# smash.net
KiCad netlist of a schematic drawn in EAGLE
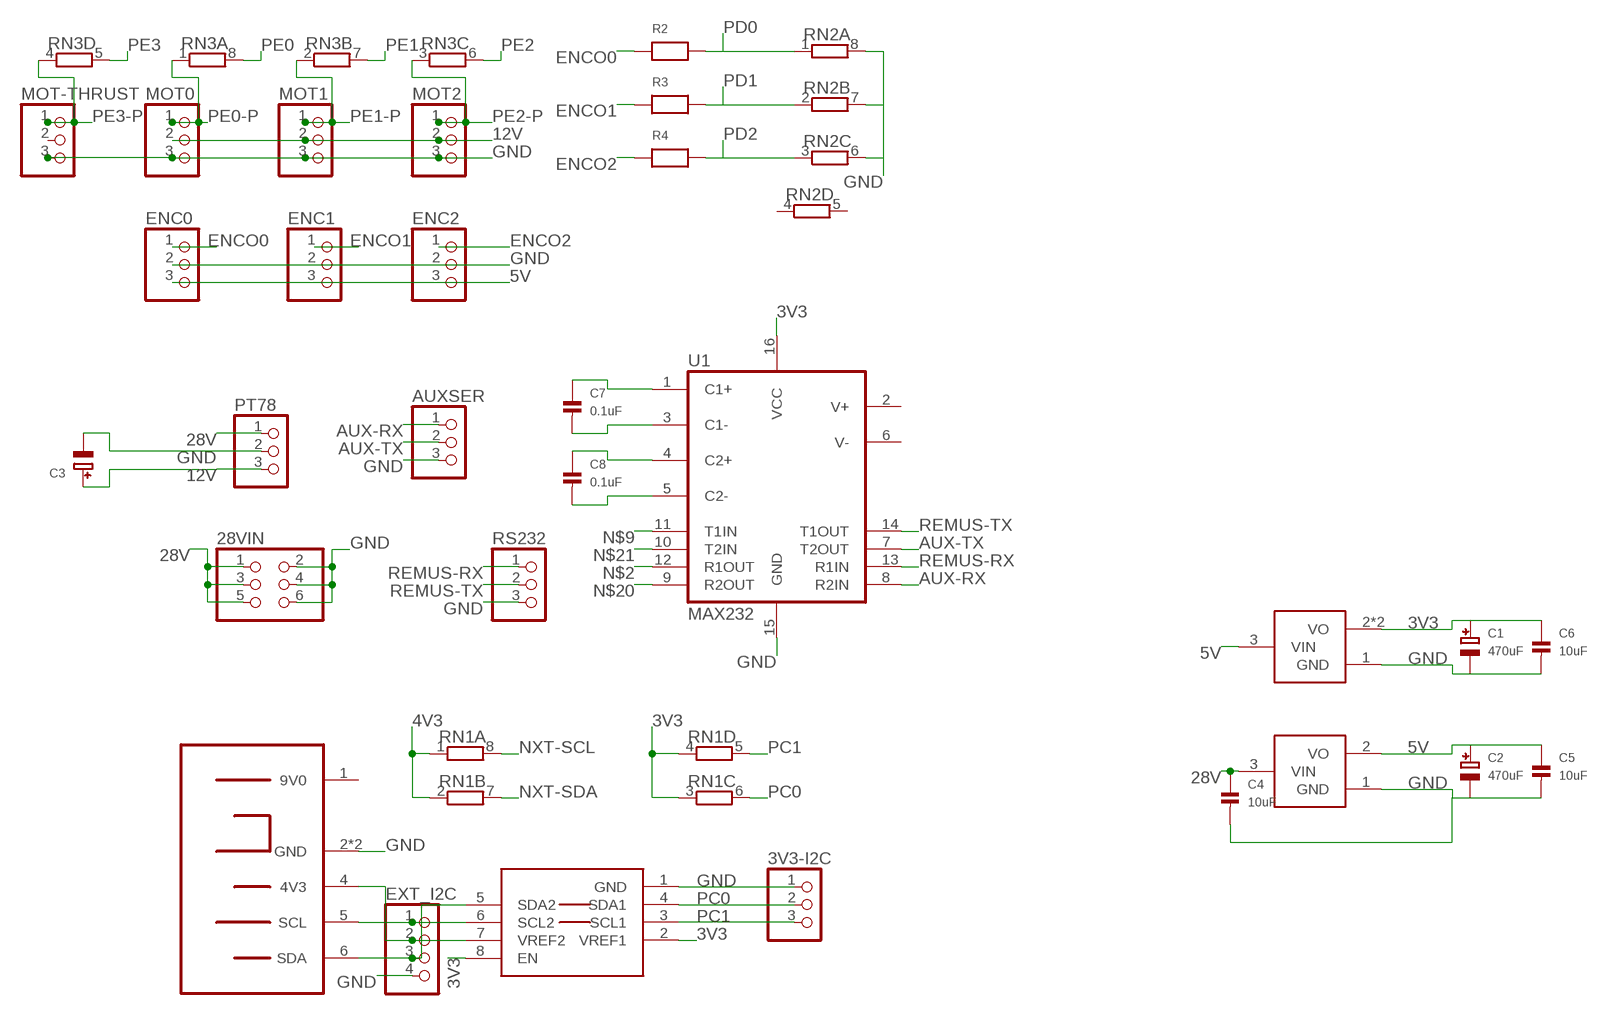
[diagram p0: schematic, sheet 1]
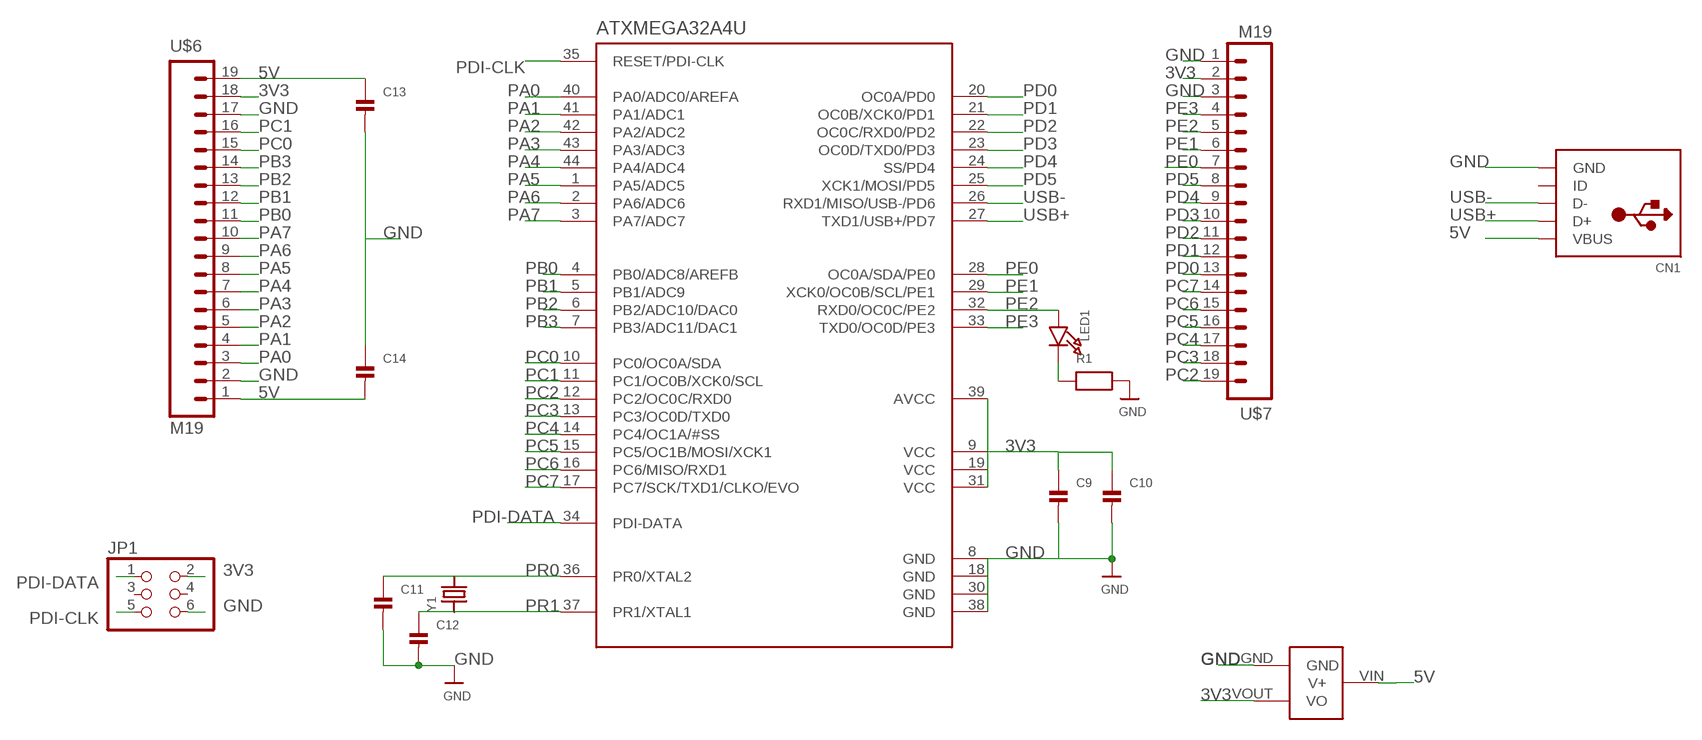
[diagram p1: schematic, sheet 2]

(export (version "E")
  (design (tool "Eeschema 10.0.6"))
  (components
    (comp (ref "3V3-I2C")
      (value "HEADER-1X3ROUND")
      (footprint "eagle-import:1X03_ROUND")
      (libsource (lib "eagle-import") (part "HEADER-1X3ROUND"))
    )
    (comp (ref "28VIN")
      (value "HEADER-2X3")
      (footprint "eagle-import:2X03")
      (libsource (lib "eagle-import") (part "HEADER-2X3"))
    )
    (comp (ref "AUXSER")
      (value "HEADER-1X3ROUND")
      (footprint "eagle-import:1X03_ROUND")
      (libsource (lib "eagle-import") (part "HEADER-1X3ROUND"))
    )
    (comp (ref "C1")
      (value "470uF")
      (footprint "eagle-import:EIA7343-31_D-W")
      (libsource (lib "eagle-import") (part "CAP_TANTALUMD/7343_WAVE"))
    )
    (comp (ref "C2")
      (value "470uF")
      (footprint "eagle-import:EIA7343-31_D-W")
      (libsource (lib "eagle-import") (part "CAP_TANTALUMD/7343_WAVE"))
    )
    (comp (ref "C3")
      (value "CAP_TANTALUMD/7343_WAVE")
      (footprint "eagle-import:EIA7343-31_D-W")
      (libsource (lib "eagle-import") (part "CAP_TANTALUMD/7343_WAVE"))
    )
    (comp (ref "C4")
      (value "10uF")
      (footprint "eagle-import:1206")
      (libsource (lib "eagle-import") (part "CAP_CERAMIC1206"))
    )
    (comp (ref "C5")
      (value "10uF")
      (footprint "eagle-import:1206")
      (libsource (lib "eagle-import") (part "CAP_CERAMIC1206"))
    )
    (comp (ref "C6")
      (value "10uF")
      (footprint "eagle-import:1206")
      (libsource (lib "eagle-import") (part "CAP_CERAMIC1206"))
    )
    (comp (ref "C7")
      (value "0.1uF")
      (footprint "eagle-import:0603")
      (libsource (lib "eagle-import") (part "CAP_CERAMIC0603"))
    )
    (comp (ref "C8")
      (value "0.1uF")
      (footprint "eagle-import:0603")
      (libsource (lib "eagle-import") (part "CAP_CERAMIC0603"))
    )
    (comp (ref "ENC0")
      (value "HEADER-1X3ROUND")
      (footprint "eagle-import:1X03_ROUND")
      (libsource (lib "eagle-import") (part "HEADER-1X3ROUND"))
    )
    (comp (ref "ENC1")
      (value "HEADER-1X3ROUND")
      (footprint "eagle-import:1X03_ROUND")
      (libsource (lib "eagle-import") (part "HEADER-1X3ROUND"))
    )
    (comp (ref "ENC2")
      (value "HEADER-1X3ROUND")
      (footprint "eagle-import:1X03_ROUND")
      (libsource (lib "eagle-import") (part "HEADER-1X3ROUND"))
    )
    (comp (ref "EXT_I2C")
      (value "HEADER-1X4ROUND")
      (footprint "eagle-import:1X04_ROUND")
      (libsource (lib "eagle-import") (part "HEADER-1X4ROUND"))
    )
    (comp (ref "MOT-THRUST")
      (value "HEADER-1X3ROUND")
      (footprint "eagle-import:1X03_ROUND")
      (libsource (lib "eagle-import") (part "HEADER-1X3ROUND"))
    )
    (comp (ref "MOT0")
      (value "HEADER-1X3ROUND")
      (footprint "eagle-import:1X03_ROUND")
      (libsource (lib "eagle-import") (part "HEADER-1X3ROUND"))
    )
    (comp (ref "MOT1")
      (value "HEADER-1X3ROUND")
      (footprint "eagle-import:1X03_ROUND")
      (libsource (lib "eagle-import") (part "HEADER-1X3ROUND"))
    )
    (comp (ref "MOT2")
      (value "HEADER-1X3ROUND")
      (footprint "eagle-import:1X03_ROUND")
      (libsource (lib "eagle-import") (part "HEADER-1X3ROUND"))
    )
    (comp (ref "PT78")
      (value "HEADER-1X3ROUND")
      (footprint "eagle-import:1X03_ROUND")
      (libsource (lib "eagle-import") (part "HEADER-1X3ROUND"))
    )
    (comp (ref "R2")
      (value "RESISTOR0603")
      (footprint "eagle-import:0603")
      (libsource (lib "eagle-import") (part "RESISTOR0603"))
    )
    (comp (ref "R3")
      (value "RESISTOR0603")
      (footprint "eagle-import:0603")
      (libsource (lib "eagle-import") (part "RESISTOR0603"))
    )
    (comp (ref "R4")
      (value "RESISTOR0603")
      (footprint "eagle-import:0603")
      (libsource (lib "eagle-import") (part "RESISTOR0603"))
    )
    (comp (ref "RN1")
      (value "RNETWORK")
      (footprint "eagle-import:RN8P-4R-CRA06S")
      (libsource (lib "eagle-import") (part "RNETWORK"))
    )
    (comp (ref "RN2")
      (value "RNETWORK")
      (footprint "eagle-import:RN8P-4R-CRA06S")
      (libsource (lib "eagle-import") (part "RNETWORK"))
    )
    (comp (ref "RN3")
      (value "RNETWORK")
      (footprint "eagle-import:RN8P-4R-CRA06S")
      (libsource (lib "eagle-import") (part "RNETWORK"))
    )
    (comp (ref "RS232")
      (value "HEADER-1X3ROUND")
      (footprint "eagle-import:1X03_ROUND")
      (libsource (lib "eagle-import") (part "HEADER-1X3ROUND"))
    )
    (comp (ref "U$1")
      (value "PCA9306")
      (footprint "eagle-import:SO-08")
      (libsource (lib "eagle-import") (part "PCA9306"))
    )
    (comp (ref "U$2")
      (value "NXT-CONNECTOR")
      (footprint "eagle-import:NXT-FOOTPRINT")
      (libsource (lib "eagle-import") (part "NXT-CONNECTOR"))
    )
    (comp (ref "U$3")
      (value "VREGAP1117")
      (footprint "eagle-import:SOT223")
      (libsource (lib "eagle-import") (part "VREGAP1117"))
    )
    (comp (ref "U$4")
      (value "VREGIFX27001")
      (footprint "eagle-import:TO252")
      (libsource (lib "eagle-import") (part "VREGIFX27001"))
    )
    (comp (ref "U1")
      (value "MAX232")
      (footprint "eagle-import:SO-16")
      (libsource (lib "eagle-import") (part "MAX232"))
    )
    (comp (ref "ATXMEGA32A4U")
      (value "ATXMEGAXXA4U-AU")
      (footprint "eagle-import:TQFP-44")
      (libsource (lib "eagle-import") (part "ATXMEGAXXA4U-AU"))
    )
    (comp (ref "C9")
      (value "CAP_CERAMIC0603")
      (footprint "eagle-import:0603")
      (libsource (lib "eagle-import") (part "CAP_CERAMIC0603"))
    )
    (comp (ref "C10")
      (value "CAP_CERAMIC0603")
      (footprint "eagle-import:0603")
      (libsource (lib "eagle-import") (part "CAP_CERAMIC0603"))
    )
    (comp (ref "C11")
      (value "CAP_CERAMIC0603")
      (footprint "eagle-import:0603")
      (libsource (lib "eagle-import") (part "CAP_CERAMIC0603"))
    )
    (comp (ref "C12")
      (value "CAP_CERAMIC0603")
      (footprint "eagle-import:0603")
      (libsource (lib "eagle-import") (part "CAP_CERAMIC0603"))
    )
    (comp (ref "C13")
      (value "CAP_CERAMIC0603")
      (footprint "eagle-import:0603")
      (libsource (lib "eagle-import") (part "CAP_CERAMIC0603"))
    )
    (comp (ref "C14")
      (value "CAP_CERAMIC0603")
      (footprint "eagle-import:0603")
      (libsource (lib "eagle-import") (part "CAP_CERAMIC0603"))
    )
    (comp (ref "CN1")
      (value "USBMICROB")
      (footprint "eagle-import:USB-MICROB")
      (libsource (lib "eagle-import") (part "USBMICROB"))
    )
    (comp (ref "JP1")
      (value "HEADER-2X3")
      (footprint "eagle-import:2X03")
      (libsource (lib "eagle-import") (part "HEADER-2X3"))
    )
    (comp (ref "LED1")
      (value "LED0603")
      (footprint "eagle-import:CHIPLED_0603")
      (libsource (lib "eagle-import") (part "LED0603"))
    )
    (comp (ref "R1")
      (value "RESISTOR0603")
      (footprint "eagle-import:0603")
      (libsource (lib "eagle-import") (part "RESISTOR0603"))
    )
    (comp (ref "U$5")
      (value "MCP1700")
      (footprint "eagle-import:SOT23-3")
      (libsource (lib "eagle-import") (part "MCP1700"))
    )
    (comp (ref "U$6")
      (value "M19")
      (footprint "eagle-import:1X19")
      (libsource (lib "eagle-import") (part "M19"))
    )
    (comp (ref "U$7")
      (value "M19")
      (footprint "eagle-import:1X19")
      (libsource (lib "eagle-import") (part "M19"))
    )
    (comp (ref "Y1")
      (value "CRYSTAL")
      (footprint "eagle-import:NX8045GB")
      (libsource (lib "eagle-import") (part "CRYSTAL"))
    )
  )
  (nets
    (net (code "1") (name "3V3") (class "Default")
      (node (ref "ATXMEGA32A4U") (pin "19") (pinfunction "VCC_19") (pintype "power_in"))
      (node (ref "ATXMEGA32A4U") (pin "31") (pinfunction "VCC_31") (pintype "power_in"))
      (node (ref "ATXMEGA32A4U") (pin "39") (pinfunction "AVCC_39") (pintype "power_in"))
      (node (ref "ATXMEGA32A4U") (pin "9") (pinfunction "VCC_9") (pintype "power_in"))
      (node (ref "C1") (pin "+") (pinfunction "+_+") (pintype "passive"))
      (node (ref "C10") (pin "1") (pinfunction "P$1_1") (pintype "passive"))
      (node (ref "C6") (pin "1") (pinfunction "P$1_1") (pintype "passive"))
      (node (ref "C9") (pin "1") (pinfunction "P$1_1") (pintype "passive"))
      (node (ref "JP1") (pin "2") (pinfunction "2_2") (pintype "passive"))
      (node (ref "RN1") (pin "3") (pinfunction "1_3") (pintype "passive"))
      (node (ref "RN1") (pin "4") (pinfunction "1_4") (pintype "passive"))
      (node (ref "U$1") (pin "2") (pinfunction "VREF1_2") (pintype "bidirectional"))
      (node (ref "U$1") (pin "8") (pinfunction "EN_8") (pintype "bidirectional"))
      (node (ref "U$3") (pin "2") (pinfunction "VO_2") (pintype "bidirectional"))
      (node (ref "U$3") (pin "4") (pinfunction "VO_4") (pintype "bidirectional"))
      (node (ref "U$5") (pin "VOUT") (pinfunction "VO_VOUT") (pintype "bidirectional"))
      (node (ref "U$6") (pin "18") (pinfunction "18_18") (pintype "passive"))
      (node (ref "U$7") (pin "2") (pinfunction "2_2") (pintype "passive"))
      (node (ref "U1") (pin "16") (pinfunction "VCC_16") (pintype "bidirectional"))
    )
    (net (code "2") (name "4V3") (class "Default")
      (node (ref "EXT_I2C") (pin "2") (pinfunction "2_2") (pintype "passive"))
      (node (ref "RN1") (pin "1") (pinfunction "1_1") (pintype "passive"))
      (node (ref "RN1") (pin "2") (pinfunction "1_2") (pintype "passive"))
      (node (ref "U$1") (pin "7") (pinfunction "VREF2_7") (pintype "bidirectional"))
      (node (ref "U$2") (pin "4") (pinfunction "4V3_4") (pintype "bidirectional"))
    )
    (net (code "3") (name "5V") (class "Default")
      (node (ref "C13") (pin "1") (pinfunction "P$1_1") (pintype "passive"))
      (node (ref "C14") (pin "2") (pinfunction "P$2_2") (pintype "passive"))
      (node (ref "C2") (pin "+") (pinfunction "+_+") (pintype "passive"))
      (node (ref "C5") (pin "1") (pinfunction "P$1_1") (pintype "passive"))
      (node (ref "CN1") (pin "P1") (pinfunction "VBUS_P1") (pintype "power_in"))
      (node (ref "ENC0") (pin "3") (pinfunction "3_3") (pintype "passive"))
      (node (ref "ENC1") (pin "3") (pinfunction "3_3") (pintype "passive"))
      (node (ref "ENC2") (pin "3") (pinfunction "3_3") (pintype "passive"))
      (node (ref "U$3") (pin "3") (pinfunction "VIN_3") (pintype "bidirectional"))
      (node (ref "U$4") (pin "2") (pinfunction "VO_2") (pintype "bidirectional"))
      (node (ref "U$5") (pin "VIN") (pinfunction "V+_VIN") (pintype "bidirectional"))
      (node (ref "U$6") (pin "1") (pinfunction "1_1") (pintype "passive"))
      (node (ref "U$6") (pin "19") (pinfunction "19_19") (pintype "passive"))
    )
    (net (code "4") (name "12V") (class "Default")
      (node (ref "C3") (pin "+") (pinfunction "+_+") (pintype "passive"))
      (node (ref "MOT0") (pin "2") (pinfunction "2_2") (pintype "passive"))
      (node (ref "MOT1") (pin "2") (pinfunction "2_2") (pintype "passive"))
      (node (ref "MOT2") (pin "2") (pinfunction "2_2") (pintype "passive"))
      (node (ref "PT78") (pin "3") (pinfunction "3_3") (pintype "passive"))
    )
    (net (code "5") (name "28V") (class "Default")
      (node (ref "28VIN") (pin "1") (pinfunction "1_1") (pintype "passive"))
      (node (ref "28VIN") (pin "3") (pinfunction "3_3") (pintype "passive"))
      (node (ref "28VIN") (pin "5") (pinfunction "5_5") (pintype "passive"))
      (node (ref "C4") (pin "1") (pinfunction "P$1_1") (pintype "passive"))
      (node (ref "PT78") (pin "1") (pinfunction "1_1") (pintype "passive"))
      (node (ref "U$4") (pin "3") (pinfunction "VIN_3") (pintype "bidirectional"))
    )
    (net (code "6") (name "AUX-RX") (class "Default")
      (node (ref "AUXSER") (pin "1") (pinfunction "1_1") (pintype "passive"))
      (node (ref "U1") (pin "8") (pinfunction "R2IN_8") (pintype "input"))
    )
    (net (code "7") (name "AUX-TX") (class "Default")
      (node (ref "AUXSER") (pin "2") (pinfunction "2_2") (pintype "passive"))
      (node (ref "U1") (pin "7") (pinfunction "T2OUT_7") (pintype "output"))
    )
    (net (code "8") (name "ENCO0") (class "Default")
      (node (ref "ENC0") (pin "1") (pinfunction "1_1") (pintype "passive"))
      (node (ref "R2") (pin "1") (pinfunction "1_1") (pintype "passive"))
    )
    (net (code "9") (name "ENCO1") (class "Default")
      (node (ref "ENC1") (pin "1") (pinfunction "1_1") (pintype "passive"))
      (node (ref "R3") (pin "1") (pinfunction "1_1") (pintype "passive"))
    )
    (net (code "10") (name "ENCO2") (class "Default")
      (node (ref "ENC2") (pin "1") (pinfunction "1_1") (pintype "passive"))
      (node (ref "R4") (pin "1") (pinfunction "1_1") (pintype "passive"))
    )
    (net (code "11") (name "GND") (class "Default")
      (node (ref "28VIN") (pin "2") (pinfunction "2_2") (pintype "passive"))
      (node (ref "28VIN") (pin "4") (pinfunction "4_4") (pintype "passive"))
      (node (ref "28VIN") (pin "6") (pinfunction "6_6") (pintype "passive"))
      (node (ref "3V3-I2C") (pin "1") (pinfunction "1_1") (pintype "passive"))
      (node (ref "ATXMEGA32A4U") (pin "18") (pinfunction "GND_18") (pintype "power_in"))
      (node (ref "ATXMEGA32A4U") (pin "30") (pinfunction "GND_30") (pintype "power_in"))
      (node (ref "ATXMEGA32A4U") (pin "38") (pinfunction "GND_38") (pintype "power_in"))
      (node (ref "ATXMEGA32A4U") (pin "8") (pinfunction "GND_8") (pintype "power_in"))
      (node (ref "AUXSER") (pin "3") (pinfunction "3_3") (pintype "passive"))
      (node (ref "C1") (pin "-") (pinfunction "-_-") (pintype "passive"))
      (node (ref "C10") (pin "2") (pinfunction "P$2_2") (pintype "passive"))
      (node (ref "C11") (pin "2") (pinfunction "P$2_2") (pintype "passive"))
      (node (ref "C12") (pin "2") (pinfunction "P$2_2") (pintype "passive"))
      (node (ref "C13") (pin "2") (pinfunction "P$2_2") (pintype "passive"))
      (node (ref "C14") (pin "1") (pinfunction "P$1_1") (pintype "passive"))
      (node (ref "C3") (pin "-") (pinfunction "-_-") (pintype "passive"))
      (node (ref "C4") (pin "2") (pinfunction "P$2_2") (pintype "passive"))
      (node (ref "C5") (pin "2") (pinfunction "P$2_2") (pintype "passive"))
      (node (ref "C6") (pin "2") (pinfunction "P$2_2") (pintype "passive"))
      (node (ref "C9") (pin "2") (pinfunction "P$2_2") (pintype "passive"))
      (node (ref "CN1") (pin "P5") (pinfunction "GND_P5") (pintype "power_in"))
      (node (ref "ENC0") (pin "2") (pinfunction "2_2") (pintype "passive"))
      (node (ref "ENC1") (pin "2") (pinfunction "2_2") (pintype "passive"))
      (node (ref "ENC2") (pin "2") (pinfunction "2_2") (pintype "passive"))
      (node (ref "EXT_I2C") (pin "4") (pinfunction "4_4") (pintype "passive"))
      (node (ref "JP1") (pin "6") (pinfunction "6_6") (pintype "passive"))
      (node (ref "MOT-THRUST") (pin "3") (pinfunction "3_3") (pintype "passive"))
      (node (ref "MOT0") (pin "3") (pinfunction "3_3") (pintype "passive"))
      (node (ref "MOT1") (pin "3") (pinfunction "3_3") (pintype "passive"))
      (node (ref "MOT2") (pin "3") (pinfunction "3_3") (pintype "passive"))
      (node (ref "PT78") (pin "2") (pinfunction "2_2") (pintype "passive"))
      (node (ref "R1") (pin "2") (pinfunction "2_2") (pintype "passive"))
      (node (ref "RN2") (pin "6") (pinfunction "2_6") (pintype "passive"))
      (node (ref "RN2") (pin "7") (pinfunction "2_7") (pintype "passive"))
      (node (ref "RN2") (pin "8") (pinfunction "2_8") (pintype "passive"))
      (node (ref "RS232") (pin "3") (pinfunction "3_3") (pintype "passive"))
      (node (ref "U$1") (pin "1") (pinfunction "GND_1") (pintype "bidirectional"))
      (node (ref "U$2") (pin "2") (pinfunction "GND_2") (pintype "bidirectional"))
      (node (ref "U$2") (pin "3") (pinfunction "GND_3") (pintype "bidirectional"))
      (node (ref "U$3") (pin "1") (pinfunction "GND_1") (pintype "bidirectional"))
      (node (ref "U$4") (pin "1") (pinfunction "GND_1") (pintype "bidirectional"))
      (node (ref "U$5") (pin "GND") (pinfunction "GND_GND") (pintype "bidirectional"))
      (node (ref "U$6") (pin "17") (pinfunction "17_17") (pintype "passive"))
      (node (ref "U$6") (pin "2") (pinfunction "2_2") (pintype "passive"))
      (node (ref "U$7") (pin "1") (pinfunction "1_1") (pintype "passive"))
      (node (ref "U$7") (pin "3") (pinfunction "3_3") (pintype "passive"))
      (node (ref "U1") (pin "15") (pinfunction "GND_15") (pintype "bidirectional"))
    )
    (net (code "12") (name "N$2") (class "Default")
      (node (ref "U1") (pin "12") (pinfunction "R1OUT_12") (pintype "output"))
    )
    (net (code "13") (name "N$9") (class "Default")
      (node (ref "U1") (pin "11") (pinfunction "T1IN_11") (pintype "input"))
    )
    (net (code "14") (name "N$20") (class "Default")
      (node (ref "U1") (pin "9") (pinfunction "R2OUT_9") (pintype "output"))
    )
    (net (code "15") (name "N$21") (class "Default")
      (node (ref "U1") (pin "10") (pinfunction "T2IN_10") (pintype "input"))
    )
    (net (code "16") (name "NXT-SCL") (class "Default")
      (node (ref "EXT_I2C") (pin "1") (pinfunction "1_1") (pintype "passive"))
      (node (ref "RN1") (pin "8") (pinfunction "2_8") (pintype "passive"))
      (node (ref "U$1") (pin "6") (pinfunction "SCL2_6") (pintype "bidirectional"))
      (node (ref "U$2") (pin "5") (pinfunction "SCL_5") (pintype "bidirectional"))
    )
    (net (code "17") (name "NXT-SDA") (class "Default")
      (node (ref "EXT_I2C") (pin "3") (pinfunction "3_3") (pintype "passive"))
      (node (ref "RN1") (pin "7") (pinfunction "2_7") (pintype "passive"))
      (node (ref "U$1") (pin "5") (pinfunction "SDA2_5") (pintype "bidirectional"))
      (node (ref "U$2") (pin "6") (pinfunction "SDA_6") (pintype "bidirectional"))
    )
    (net (code "18") (name "Net-(C7-P$1)") (class "Default")
      (node (ref "C7") (pin "1") (pinfunction "P$1_1") (pintype "passive"))
      (node (ref "U1") (pin "1") (pinfunction "C1+_1") (pintype "bidirectional"))
    )
    (net (code "19") (name "Net-(C7-P$2)") (class "Default")
      (node (ref "C7") (pin "2") (pinfunction "P$2_2") (pintype "passive"))
      (node (ref "U1") (pin "3") (pinfunction "C1-_3") (pintype "bidirectional"))
    )
    (net (code "20") (name "Net-(C8-P$1)") (class "Default")
      (node (ref "C8") (pin "1") (pinfunction "P$1_1") (pintype "passive"))
      (node (ref "U1") (pin "4") (pinfunction "C2+_4") (pintype "bidirectional"))
    )
    (net (code "21") (name "Net-(C8-P$2)") (class "Default")
      (node (ref "C8") (pin "2") (pinfunction "P$2_2") (pintype "passive"))
      (node (ref "U1") (pin "5") (pinfunction "C2-_5") (pintype "bidirectional"))
    )
    (net (code "22") (name "Net-(LED1-PadC)") (class "Default")
      (node (ref "LED1") (pin "C") (pinfunction "C_C") (pintype "passive"))
      (node (ref "R1") (pin "1") (pinfunction "1_1") (pintype "passive"))
    )
    (net (code "23") (name "PA0") (class "Default")
      (node (ref "ATXMEGA32A4U") (pin "40") (pinfunction "PA0/ADC0/AREFA_40") (pintype "bidirectional"))
      (node (ref "U$6") (pin "3") (pinfunction "3_3") (pintype "passive"))
    )
    (net (code "24") (name "PA1") (class "Default")
      (node (ref "ATXMEGA32A4U") (pin "41") (pinfunction "PA1/ADC1_41") (pintype "bidirectional"))
      (node (ref "U$6") (pin "4") (pinfunction "4_4") (pintype "passive"))
    )
    (net (code "25") (name "PA2") (class "Default")
      (node (ref "ATXMEGA32A4U") (pin "42") (pinfunction "PA2/ADC2_42") (pintype "bidirectional"))
      (node (ref "U$6") (pin "5") (pinfunction "5_5") (pintype "passive"))
    )
    (net (code "26") (name "PA3") (class "Default")
      (node (ref "ATXMEGA32A4U") (pin "43") (pinfunction "PA3/ADC3_43") (pintype "bidirectional"))
      (node (ref "U$6") (pin "6") (pinfunction "6_6") (pintype "passive"))
    )
    (net (code "27") (name "PA4") (class "Default")
      (node (ref "ATXMEGA32A4U") (pin "44") (pinfunction "PA4/ADC4_44") (pintype "bidirectional"))
      (node (ref "U$6") (pin "7") (pinfunction "7_7") (pintype "passive"))
    )
    (net (code "28") (name "PA5") (class "Default")
      (node (ref "ATXMEGA32A4U") (pin "1") (pinfunction "PA5/ADC5_1") (pintype "bidirectional"))
      (node (ref "U$6") (pin "8") (pinfunction "8_8") (pintype "passive"))
    )
    (net (code "29") (name "PA6") (class "Default")
      (node (ref "ATXMEGA32A4U") (pin "2") (pinfunction "PA6/ADC6_2") (pintype "bidirectional"))
      (node (ref "U$6") (pin "9") (pinfunction "9_9") (pintype "passive"))
    )
    (net (code "30") (name "PA7") (class "Default")
      (node (ref "ATXMEGA32A4U") (pin "3") (pinfunction "PA7/ADC7_3") (pintype "bidirectional"))
      (node (ref "U$6") (pin "10") (pinfunction "10_10") (pintype "passive"))
    )
    (net (code "31") (name "PB0") (class "Default")
      (node (ref "ATXMEGA32A4U") (pin "4") (pinfunction "PB0/ADC8/AREFB_4") (pintype "bidirectional"))
      (node (ref "U$6") (pin "11") (pinfunction "11_11") (pintype "passive"))
    )
    (net (code "32") (name "PB1") (class "Default")
      (node (ref "ATXMEGA32A4U") (pin "5") (pinfunction "PB1/ADC9_5") (pintype "bidirectional"))
      (node (ref "U$6") (pin "12") (pinfunction "12_12") (pintype "passive"))
    )
    (net (code "33") (name "PB2") (class "Default")
      (node (ref "ATXMEGA32A4U") (pin "6") (pinfunction "PB2/ADC10/DAC0_6") (pintype "bidirectional"))
      (node (ref "U$6") (pin "13") (pinfunction "13_13") (pintype "passive"))
    )
    (net (code "34") (name "PB3") (class "Default")
      (node (ref "ATXMEGA32A4U") (pin "7") (pinfunction "PB3/ADC11/DAC1_7") (pintype "bidirectional"))
      (node (ref "U$6") (pin "14") (pinfunction "14_14") (pintype "passive"))
    )
    (net (code "35") (name "PC0") (class "Default")
      (node (ref "3V3-I2C") (pin "2") (pinfunction "2_2") (pintype "passive"))
      (node (ref "ATXMEGA32A4U") (pin "10") (pinfunction "PC0/OC0A/SDA_10") (pintype "bidirectional"))
      (node (ref "RN1") (pin "6") (pinfunction "2_6") (pintype "passive"))
      (node (ref "U$1") (pin "4") (pinfunction "SDA1_4") (pintype "bidirectional"))
      (node (ref "U$6") (pin "15") (pinfunction "15_15") (pintype "passive"))
    )
    (net (code "36") (name "PC1") (class "Default")
      (node (ref "3V3-I2C") (pin "3") (pinfunction "3_3") (pintype "passive"))
      (node (ref "ATXMEGA32A4U") (pin "11") (pinfunction "PC1/OC0B/XCK0/SCL_11") (pintype "bidirectional"))
      (node (ref "RN1") (pin "5") (pinfunction "2_5") (pintype "passive"))
      (node (ref "U$1") (pin "3") (pinfunction "SCL1_3") (pintype "bidirectional"))
      (node (ref "U$6") (pin "16") (pinfunction "16_16") (pintype "passive"))
    )
    (net (code "37") (name "PC2") (class "Default")
      (node (ref "ATXMEGA32A4U") (pin "12") (pinfunction "PC2/OC0C/RXD0_12") (pintype "bidirectional"))
      (node (ref "U$7") (pin "19") (pinfunction "19_19") (pintype "passive"))
    )
    (net (code "38") (name "PC3") (class "Default")
      (node (ref "ATXMEGA32A4U") (pin "13") (pinfunction "PC3/OC0D/TXD0_13") (pintype "bidirectional"))
      (node (ref "U$7") (pin "18") (pinfunction "18_18") (pintype "passive"))
    )
    (net (code "39") (name "PC4") (class "Default")
      (node (ref "ATXMEGA32A4U") (pin "14") (pinfunction "PC4/OC1A/#SS_14") (pintype "bidirectional"))
      (node (ref "U$7") (pin "17") (pinfunction "17_17") (pintype "passive"))
    )
    (net (code "40") (name "PC5") (class "Default")
      (node (ref "ATXMEGA32A4U") (pin "15") (pinfunction "PC5/OC1B/MOSI/XCK1_15") (pintype "bidirectional"))
      (node (ref "U$7") (pin "16") (pinfunction "16_16") (pintype "passive"))
    )
    (net (code "41") (name "PC6") (class "Default")
      (node (ref "ATXMEGA32A4U") (pin "16") (pinfunction "PC6/MISO/RXD1_16") (pintype "bidirectional"))
      (node (ref "U$7") (pin "15") (pinfunction "15_15") (pintype "passive"))
    )
    (net (code "42") (name "PC7") (class "Default")
      (node (ref "ATXMEGA32A4U") (pin "17") (pinfunction "PC7/SCK/TXD1/CLKO/EVO_17") (pintype "bidirectional"))
      (node (ref "U$7") (pin "14") (pinfunction "14_14") (pintype "passive"))
    )
    (net (code "43") (name "PD0") (class "Default")
      (node (ref "ATXMEGA32A4U") (pin "20") (pinfunction "OC0A/PD0_20") (pintype "bidirectional"))
      (node (ref "R2") (pin "2") (pinfunction "2_2") (pintype "passive"))
      (node (ref "RN2") (pin "1") (pinfunction "1_1") (pintype "passive"))
      (node (ref "U$7") (pin "13") (pinfunction "13_13") (pintype "passive"))
    )
    (net (code "44") (name "PD1") (class "Default")
      (node (ref "ATXMEGA32A4U") (pin "21") (pinfunction "OC0B/XCK0/PD1_21") (pintype "bidirectional"))
      (node (ref "R3") (pin "2") (pinfunction "2_2") (pintype "passive"))
      (node (ref "RN2") (pin "2") (pinfunction "1_2") (pintype "passive"))
      (node (ref "U$7") (pin "12") (pinfunction "12_12") (pintype "passive"))
    )
    (net (code "45") (name "PD2") (class "Default")
      (node (ref "ATXMEGA32A4U") (pin "22") (pinfunction "OC0C/RXD0/PD2_22") (pintype "bidirectional"))
      (node (ref "R4") (pin "2") (pinfunction "2_2") (pintype "passive"))
      (node (ref "RN2") (pin "3") (pinfunction "1_3") (pintype "passive"))
      (node (ref "U$7") (pin "11") (pinfunction "11_11") (pintype "passive"))
    )
    (net (code "46") (name "PD3") (class "Default")
      (node (ref "ATXMEGA32A4U") (pin "23") (pinfunction "OC0D/TXD0/PD3_23") (pintype "bidirectional"))
      (node (ref "U$7") (pin "10") (pinfunction "10_10") (pintype "passive"))
    )
    (net (code "47") (name "PD4") (class "Default")
      (node (ref "ATXMEGA32A4U") (pin "24") (pinfunction "SS/PD4_24") (pintype "bidirectional"))
      (node (ref "U$7") (pin "9") (pinfunction "9_9") (pintype "passive"))
    )
    (net (code "48") (name "PD5") (class "Default")
      (node (ref "ATXMEGA32A4U") (pin "25") (pinfunction "XCK1/MOSI/PD5_25") (pintype "bidirectional"))
      (node (ref "U$7") (pin "8") (pinfunction "8_8") (pintype "passive"))
    )
    (net (code "49") (name "PDI-CLK") (class "Default")
      (node (ref "ATXMEGA32A4U") (pin "35") (pinfunction "RESET/PDI-CLK_35") (pintype "input"))
      (node (ref "JP1") (pin "5") (pinfunction "5_5") (pintype "passive"))
    )
    (net (code "50") (name "PDI-DATA") (class "Default")
      (node (ref "ATXMEGA32A4U") (pin "34") (pinfunction "PDI-DATA_34") (pintype "bidirectional"))
      (node (ref "JP1") (pin "1") (pinfunction "1_1") (pintype "passive"))
    )
    (net (code "51") (name "PE0") (class "Default")
      (node (ref "ATXMEGA32A4U") (pin "28") (pinfunction "OC0A/SDA/PE0_28") (pintype "bidirectional"))
      (node (ref "RN3") (pin "8") (pinfunction "2_8") (pintype "passive"))
      (node (ref "U$7") (pin "7") (pinfunction "7_7") (pintype "passive"))
    )
    (net (code "52") (name "PE0-P") (class "Default")
      (node (ref "MOT0") (pin "1") (pinfunction "1_1") (pintype "passive"))
      (node (ref "RN3") (pin "1") (pinfunction "1_1") (pintype "passive"))
    )
    (net (code "53") (name "PE1") (class "Default")
      (node (ref "ATXMEGA32A4U") (pin "29") (pinfunction "XCK0/OC0B/SCL/PE1_29") (pintype "bidirectional"))
      (node (ref "RN3") (pin "7") (pinfunction "2_7") (pintype "passive"))
      (node (ref "U$7") (pin "6") (pinfunction "6_6") (pintype "passive"))
    )
    (net (code "54") (name "PE1-P") (class "Default")
      (node (ref "MOT1") (pin "1") (pinfunction "1_1") (pintype "passive"))
      (node (ref "RN3") (pin "2") (pinfunction "1_2") (pintype "passive"))
    )
    (net (code "55") (name "PE2") (class "Default")
      (node (ref "ATXMEGA32A4U") (pin "32") (pinfunction "RXD0/OC0C/PE2_32") (pintype "bidirectional"))
      (node (ref "LED1") (pin "A") (pinfunction "A_A") (pintype "passive"))
      (node (ref "RN3") (pin "6") (pinfunction "2_6") (pintype "passive"))
      (node (ref "U$7") (pin "5") (pinfunction "5_5") (pintype "passive"))
    )
    (net (code "56") (name "PE2-P") (class "Default")
      (node (ref "MOT2") (pin "1") (pinfunction "1_1") (pintype "passive"))
      (node (ref "RN3") (pin "3") (pinfunction "1_3") (pintype "passive"))
    )
    (net (code "57") (name "PE3") (class "Default")
      (node (ref "ATXMEGA32A4U") (pin "33") (pinfunction "TXD0/OC0D/PE3_33") (pintype "bidirectional"))
      (node (ref "RN3") (pin "5") (pinfunction "2_5") (pintype "passive"))
      (node (ref "U$7") (pin "4") (pinfunction "4_4") (pintype "passive"))
    )
    (net (code "58") (name "PE3-P") (class "Default")
      (node (ref "MOT-THRUST") (pin "1") (pinfunction "1_1") (pintype "passive"))
      (node (ref "RN3") (pin "4") (pinfunction "1_4") (pintype "passive"))
    )
    (net (code "59") (name "PR0") (class "Default")
      (node (ref "ATXMEGA32A4U") (pin "36") (pinfunction "PR0/XTAL2_36") (pintype "bidirectional"))
      (node (ref "C11") (pin "1") (pinfunction "P$1_1") (pintype "passive"))
      (node (ref "Y1") (pin "P$2") (pinfunction "2_P$2") (pintype "passive"))
    )
    (net (code "60") (name "PR1") (class "Default")
      (node (ref "ATXMEGA32A4U") (pin "37") (pinfunction "PR1/XTAL1_37") (pintype "bidirectional"))
      (node (ref "C12") (pin "1") (pinfunction "P$1_1") (pintype "passive"))
      (node (ref "Y1") (pin "P$1") (pinfunction "1_P$1") (pintype "passive"))
    )
    (net (code "61") (name "REMUS-RX") (class "Default")
      (node (ref "RS232") (pin "1") (pinfunction "1_1") (pintype "passive"))
      (node (ref "U1") (pin "13") (pinfunction "R1IN_13") (pintype "input"))
    )
    (net (code "62") (name "REMUS-TX") (class "Default")
      (node (ref "RS232") (pin "2") (pinfunction "2_2") (pintype "passive"))
      (node (ref "U1") (pin "14") (pinfunction "T1OUT_14") (pintype "output"))
    )
    (net (code "63") (name "USB+") (class "Default")
      (node (ref "ATXMEGA32A4U") (pin "27") (pinfunction "TXD1/USB+/PD7_27") (pintype "bidirectional"))
      (node (ref "CN1") (pin "P3") (pinfunction "D+_P3") (pintype "bidirectional"))
    )
    (net (code "64") (name "USB-") (class "Default")
      (node (ref "ATXMEGA32A4U") (pin "26") (pinfunction "RXD1/MISO/USB-/PD6_26") (pintype "bidirectional"))
      (node (ref "CN1") (pin "P2") (pinfunction "D-_P2") (pintype "bidirectional"))
    )
    (net (code "65") (name "unconnected-(C2-Pad-)") (class "Default")
      (node (ref "C2") (pin "-") (pinfunction "-_-") (pintype "passive"))
    )
    (net (code "66") (name "unconnected-(CN1-ID-PadP4)") (class "Default")
      (node (ref "CN1") (pin "P4") (pinfunction "ID_P4") (pintype "bidirectional"))
    )
    (net (code "67") (name "unconnected-(JP1-Pad3)") (class "Default")
      (node (ref "JP1") (pin "3") (pinfunction "3_3") (pintype "passive"))
    )
    (net (code "68") (name "unconnected-(JP1-Pad4)") (class "Default")
      (node (ref "JP1") (pin "4") (pinfunction "4_4") (pintype "passive"))
    )
    (net (code "69") (name "unconnected-(MOT-THRUST-Pad2)") (class "Default")
      (node (ref "MOT-THRUST") (pin "2") (pinfunction "2_2") (pintype "passive"))
    )
    (net (code "70") (name "unconnected-(RN2D-1-Pad4)") (class "Default")
      (node (ref "RN2") (pin "4") (pinfunction "1_4") (pintype "passive"))
    )
    (net (code "71") (name "unconnected-(RN2D-2-Pad5)") (class "Default")
      (node (ref "RN2") (pin "5") (pinfunction "2_5") (pintype "passive"))
    )
    (net (code "72") (name "unconnected-(U$2-9V0-Pad1)") (class "Default")
      (node (ref "U$2") (pin "1") (pinfunction "9V0_1") (pintype "bidirectional"))
    )
    (net (code "73") (name "unconnected-(U1-V+-Pad2)") (class "Default")
      (node (ref "U1") (pin "2") (pinfunction "V+_2") (pintype "bidirectional"))
    )
    (net (code "74") (name "unconnected-(U1-V--Pad6)") (class "Default")
      (node (ref "U1") (pin "6") (pinfunction "V-_6") (pintype "bidirectional"))
    )
  )
)
